# transmitter.net
KiCad netlist of a schematic drawn in EAGLE
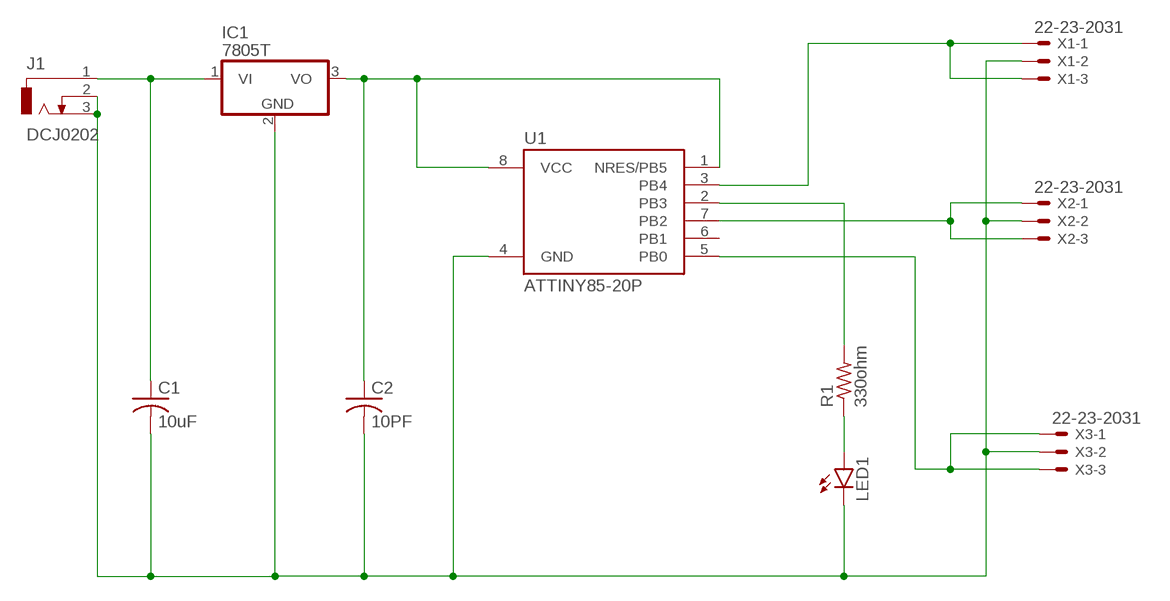
[diagram p0: schematic, sheet 1]

(export (version "E")
  (design (tool "Eeschema 10.0.6"))
  (components
    (comp (ref "C1")
      (value "10uF")
      (footprint "eagle-import:C025-024X044")
      (libsource (lib "eagle-import") (part "C-US025-024X044"))
    )
    (comp (ref "C2")
      (value "10PF")
      (footprint "eagle-import:C025-024X044")
      (libsource (lib "eagle-import") (part "C-US025-024X044"))
    )
    (comp (ref "IC1")
      (value "7805T")
      (footprint "eagle-import:TO220H")
      (libsource (lib "eagle-import") (part "78T05"))
    )
    (comp (ref "J1")
      (value "DCJ0202")
      (footprint "eagle-import:DCJ0202")
      (libsource (lib "eagle-import") (part "DCJ0202"))
    )
    (comp (ref "LED1")
      (value "LED3MM")
      (footprint "eagle-import:LED3MM")
      (libsource (lib "eagle-import") (part "LED3MM"))
    )
    (comp (ref "R1")
      (value "330ohm")
      (footprint "eagle-import:0207_5V")
      (libsource (lib "eagle-import") (part "R-US_0207/5V"))
    )
    (comp (ref "U1")
      (value "ATTINY85-20P")
      (footprint "eagle-import:PDIP08_300MIL")
      (libsource (lib "eagle-import") (part "ATTINY85P-20"))
    )
    (comp (ref "X1")
      (value "22-23-2031")
      (footprint "eagle-import:22-23-2031")
      (fields (field (name "MF") "MOLEX"))
      (libsource (lib "eagle-import") (part "22-23-2031"))
    )
    (comp (ref "X2")
      (value "22-23-2031")
      (footprint "eagle-import:22-23-2031")
      (fields (field (name "MF") "MOLEX"))
      (libsource (lib "eagle-import") (part "22-23-2031"))
    )
    (comp (ref "X3")
      (value "22-23-2031")
      (footprint "eagle-import:22-23-2031")
      (fields (field (name "MF") "MOLEX"))
      (libsource (lib "eagle-import") (part "22-23-2031"))
    )
  )
  (nets
    (net (code "1") (name "Net-(IC1-GND)") (class "Default")
      (node (ref "C1") (pin "2") (pinfunction "2_2") (pintype "passive"))
      (node (ref "C2") (pin "2") (pinfunction "2_2") (pintype "passive"))
      (node (ref "IC1") (pin "2") (pinfunction "GND_2") (pintype "passive"))
      (node (ref "J1") (pin "2") (pinfunction "2_2") (pintype "passive"))
      (node (ref "J1") (pin "3") (pinfunction "3_3") (pintype "passive"))
      (node (ref "LED1") (pin "K") (pinfunction "C_K") (pintype "passive"))
      (node (ref "U1") (pin "4") (pinfunction "GND_4") (pintype "power_in"))
      (node (ref "X1") (pin "2") (pinfunction "S_2") (pintype "passive"))
      (node (ref "X2") (pin "2") (pinfunction "S_2") (pintype "passive"))
      (node (ref "X3") (pin "2") (pinfunction "S_2") (pintype "passive"))
    )
    (net (code "2") (name "Net-(IC1-VI)") (class "Default")
      (node (ref "C1") (pin "1") (pinfunction "1_1") (pintype "passive"))
      (node (ref "IC1") (pin "1") (pinfunction "VI_1") (pintype "input"))
      (node (ref "J1") (pin "1") (pinfunction "1_1") (pintype "passive"))
    )
    (net (code "3") (name "Net-(IC1-VO)") (class "Default")
      (node (ref "C2") (pin "1") (pinfunction "1_1") (pintype "passive"))
      (node (ref "IC1") (pin "3") (pinfunction "VO_3") (pintype "passive"))
      (node (ref "U1") (pin "1") (pinfunction "NRES/PB5_1") (pintype "bidirectional"))
      (node (ref "U1") (pin "8") (pinfunction "VCC_8") (pintype "power_in"))
    )
    (net (code "4") (name "Net-(LED1-PadA)") (class "Default")
      (node (ref "LED1") (pin "A") (pinfunction "A_A") (pintype "passive"))
      (node (ref "R1") (pin "1") (pinfunction "1_1") (pintype "passive"))
    )
    (net (code "5") (name "Net-(U1-PB0)") (class "Default")
      (node (ref "U1") (pin "5") (pinfunction "PB0_5") (pintype "bidirectional"))
      (node (ref "X3") (pin "1") (pinfunction "S_1") (pintype "passive"))
      (node (ref "X3") (pin "3") (pinfunction "S_3") (pintype "passive"))
    )
    (net (code "6") (name "Net-(U1-PB2)") (class "Default")
      (node (ref "U1") (pin "7") (pinfunction "PB2_7") (pintype "bidirectional"))
      (node (ref "X2") (pin "1") (pinfunction "S_1") (pintype "passive"))
      (node (ref "X2") (pin "3") (pinfunction "S_3") (pintype "passive"))
    )
    (net (code "7") (name "Net-(U1-PB3)") (class "Default")
      (node (ref "R1") (pin "2") (pinfunction "2_2") (pintype "passive"))
      (node (ref "U1") (pin "2") (pinfunction "PB3_2") (pintype "bidirectional"))
    )
    (net (code "8") (name "Net-(U1-PB4)") (class "Default")
      (node (ref "U1") (pin "3") (pinfunction "PB4_3") (pintype "bidirectional"))
      (node (ref "X1") (pin "1") (pinfunction "S_1") (pintype "passive"))
      (node (ref "X1") (pin "3") (pinfunction "S_3") (pintype "passive"))
    )
    (net (code "9") (name "unconnected-(U1-PB1-Pad6)") (class "Default")
      (node (ref "U1") (pin "6") (pinfunction "PB1_6") (pintype "bidirectional"))
    )
  )
)
